# 7_4v_BOOST.net
KiCad netlist of a schematic drawn in Altium Designer
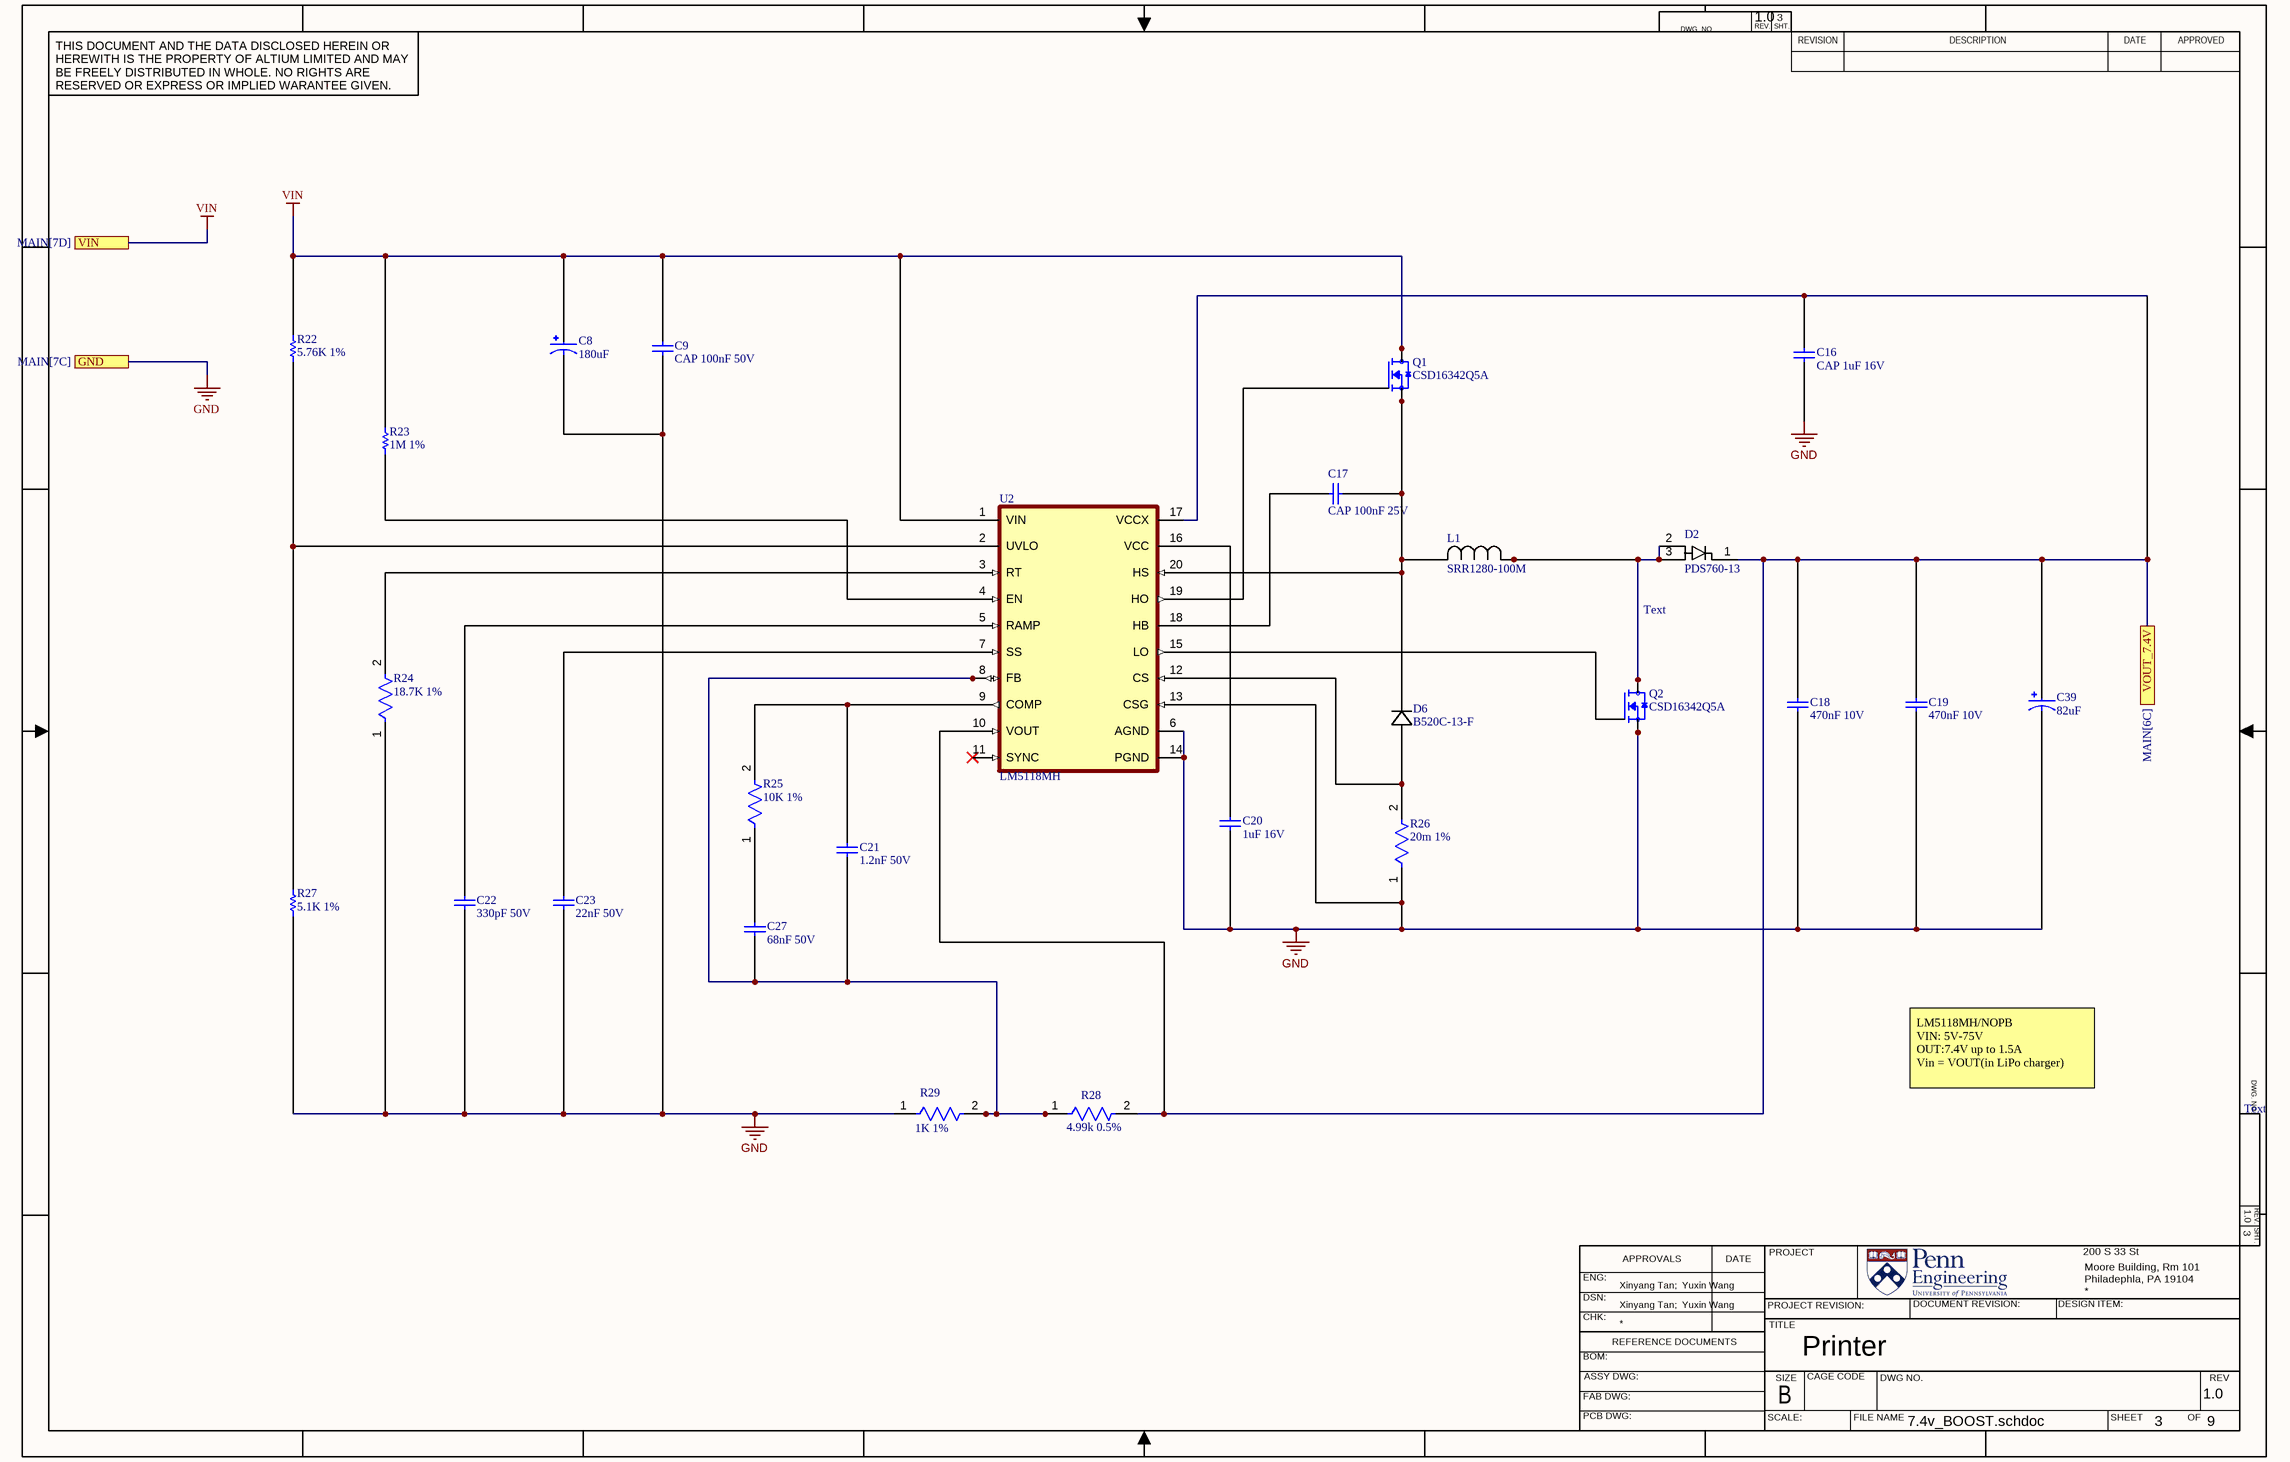
[diagram p0: 7.4v_BOOST.schdoc]

(export (version "E")
  (design (tool "Eeschema 10.0.6"))
  (components
    (comp (ref "C8")
      (value "180uF")
      (footprint "CAP_16SVPF180M")
      (fields (field (name "MP") "16SVPF180M"))
      (libsource (lib "Schematics") (part "16SVPF180M"))
    )
    (comp (ref "C9")
      (value "CAP 100nF 50V")
      (footprint "CAPC0805(2012)100_L")
      (description "CAP 100nF 50V ±5% 0805 (2012 Metric) Thickness 1mm SMD")
      (fields (field (name "TOLERANCE") "Â±5%"))
      (libsource (lib "Altium Content Vault") (part "CAP"))
    )
    (comp (ref "C16")
      (value "CAP 1uF 16V")
      (footprint "CAPC0805(2012)100_N")
      (description "CAP 1uF 16V ±5% 0805 (2012 Metric) Thickness 1mm SMD")
      (fields (field (name "TOLERANCE") "Â±5%"))
      (libsource (lib "Altium Content Vault") (part "CAP"))
    )
    (comp (ref "C17")
      (value "CAP 100nF 25V")
      (footprint "CAPC0805(2012)75_M")
      (description "CAP 100nF 25V ±20% 0805 (2012 Metric) Thickness 0.75mm SMD")
      (fields (field (name "TOLERANCE") "Â±20%"))
      (libsource (lib "Altium Content Vault") (part "CAP"))
    )
    (comp (ref "C18")
      (value "470nF 10V")
      (footprint "CAPC0402(1005)60_M")
      (description "CAP 470nF 10V -20% to +80% 0402 (1005 Metric) Thickness 0.6mm SMD")
      (fields (field (name "TOLERANCE") "-20% to +80%"))
      (libsource (lib "Altium Content Vault") (part "CAP"))
    )
    (comp (ref "C19")
      (value "470nF 10V")
      (footprint "CAPC0402(1005)60_M")
      (description "CAP 470nF 10V -20% to +80% 0402 (1005 Metric) Thickness 0.6mm SMD")
      (fields (field (name "TOLERANCE") "-20% to +80%"))
      (libsource (lib "Altium Content Vault") (part "CAP"))
    )
    (comp (ref "C20")
      (value "1uF 16V")
      (footprint "CAPC0805(2012)100_N")
      (description "CAP 1uF 16V ±5% 0805 (2012 Metric) Thickness 1mm SMD")
      (fields (field (name "TOLERANCE") "Â±5%"))
      (libsource (lib "Altium Content Vault") (part "CAP"))
    )
    (comp (ref "C21")
      (value "1.2nF 50V")
      (footprint "CAPC0805(2012)100_L")
      (description "CAP 1.2nF 50V ±10% 0805 (2012 Metric) Thickness 1mm SMD")
      (fields (field (name "TOLERANCE") "Â±10%"))
      (libsource (lib "Altium Content Vault") (part "CAP"))
    )
    (comp (ref "C22")
      (value "330pF 50V")
      (footprint "CAPC0805(2012)145_L")
      (description "CAP 330pF 50V ±5% 0805 (2012 Metric) Thickness 1.45mm SMD")
      (fields (field (name "TOLERANCE") "Â±5%"))
      (libsource (lib "Altium Content Vault") (part "CAP"))
    )
    (comp (ref "C23")
      (value "22nF 50V")
      (footprint "CAPC0805(2012)75_N")
      (description "CAP 22nF 50V ±20% 0805 (2012 Metric) Thickness 0.75mm SMD")
      (fields (field (name "TOLERANCE") "Â±20%"))
      (libsource (lib "Altium Content Vault") (part "CAP"))
    )
    (comp (ref "C27")
      (value "68nF 50V")
      (footprint "CAPC1206(3216)100_L")
      (description "CAP 68nF 50V -20% to +80% 1206 (3216 Metric) Thickness 1mm SMD")
      (fields (field (name "TOLERANCE") "-20% to +80%"))
      (libsource (lib "Altium Content Vault") (part "CAP"))
    )
    (comp (ref "C39")
      (value "82uF")
      (footprint "CHEMI-F80")
      (description "No Description Available")
      (fields
        (field (name "MANUFACTURER_PART_NUMBER") "APXE160ARA820MF80G")
        (field (name "COPYRIGHT") "Copyright (C) 2022 Ultra Librarian. All rights reserved.")
      )
      (libsource (lib "Schematics") (part "APXE160ARA820MF80G"))
    )
    (comp (ref "D2")
      (value "PDS760-13")
      (footprint "POWERDI5_DIO")
      (description "No Description Available")
      (fields (field (name "COPYRIGHT") "Copyright (C) 2022 Ultra Librarian. All rights reserved."))
      (libsource (lib "Schematics") (part "PDS760-13"))
    )
    (comp (ref "D6")
      (value "B520C-13-F")
      (footprint "SMC_DIO")
      (description "No Description Available")
      (fields (field (name "COPYRIGHT") "Copyright (C) 2022 Ultra Librarian. All rights reserved."))
      (libsource (lib "Schematics") (part "B520C-13-F"))
    )
    (comp (ref "L1")
      (value "SRR1280-100M")
      (footprint "IND_BOURNS_SRR1280")
      (description "No Description Available")
      (fields (field (name "COPYRIGHT") "Copyright (C) 2022 Ultra Librarian. All rights reserved."))
      (libsource (lib "Schematics") (part "SRR1280-100M"))
    )
    (comp (ref "Q1")
      (value "CSD16342Q5A")
      (footprint "DQJ8_TEX")
      (description "No Description Available")
      (fields (field (name "COPYRIGHT") "Copyright (C) 2022 Ultra Librarian. All rights reserved."))
      (libsource (lib "Schematics") (part "CSD16342Q5A"))
    )
    (comp (ref "Q2")
      (value "CSD16342Q5A")
      (footprint "DQJ8_TEX")
      (description "No Description Available")
      (fields (field (name "COPYRIGHT") "Copyright (C) 2022 Ultra Librarian. All rights reserved."))
      (libsource (lib "Schematics") (part "CSD16342Q5A"))
    )
    (comp (ref "R22")
      (value "5.76K 1%")
      (footprint "RESC1608X55X25ML10T15")
      (fields (field (name "PART NUMBER") "RC0603FR-075K76L") (field (name "MANUFACTURER") "Yageo"))
      (libsource (lib "Altium Content Vault") (part "RES"))
    )
    (comp (ref "R23")
      (value "1M 1%")
      (footprint "RESC1608X55X25LL10T15")
      (description "Chip Resistor, 1 MOhm, +/- 1%, 100 mW, -55 to 155 degC, 0603 (1608 Metric), RoHS, Tape and Reel")
      (fields (field (name "TOLERANCE") "20%"))
      (libsource (lib "Altium Content Vault") (part "RES-2"))
    )
    (comp (ref "R24")
      (value "18.7K 1%")
      (footprint "FP-RT0805-MFG")
      (description "RES SMD 18.7K OHM 1% 1/8W 0805")
      (fields
        (field (name "OCTOPART") "https://octopart.com/rt0805fre0718k7l-yageo-1462871")
        (field (name "TOLERANCE") "0.0001")
      )
      (libsource (lib "Altium Content Vault") (part "1029c3af85768c4190bb7ad29bc67b5"))
    )
    (comp (ref "R25")
      (value "10K 1%")
      (footprint "FP-RMCF0402-IPC_C")
      (description "10kΩ ±1% 0.063W 0402 Thick Film Chip Resistor AEC-Q200 compliant")
      (fields (field (name "TOLERANCE") "1%"))
      (libsource (lib "Altium Content Vault") (part "1029c3af85768c4190bb7ad29bc67b5"))
    )
    (comp (ref "R26")
      (value "20m 1%")
      (footprint "FP-PRL1632-IPC_B")
      (description "20 mOhms ±1% 1W Chip Resistor Wide 0612 (1632 Metric), Current Sense Thin Film")
      (fields (field (name "TOLERANCE") "1%"))
      (libsource (lib "Altium Content Vault") (part "1029c3af85768c4190bb7ad29bc67b5"))
    )
    (comp (ref "R27")
      (value "5.1K 1%")
      (footprint "RESC1608X55X25ML10T15")
      (fields (field (name "MANUFACTURER") "Yageo") (field (name "PART NUMBER") "RC0603FR-075K1L"))
      (libsource (lib "Altium Content Vault") (part "RES"))
    )
    (comp (ref "R28")
      (value "4.99k 0.5%")
      (footprint "FP-RG1608-IPC_C")
      (description "Automotive Metal Thin Film Chip Resistor, 0603, 4.99kΩ, 0.5%, 25ppm/°C, 0.1W, 100V")
      (fields (field (name "TOLERANCE") "0.5%"))
      (libsource (lib "Altium Content Vault") (part "1029c3af85768c4190bb7ad29bc67b5"))
    )
    (comp (ref "R29")
      (value "1K 1%")
      (footprint "FP-RC0603-0_55-IPC_C")
      (description "RES 1K OHM 1% 1/10W 0603")
      (fields (field (name "TOLERANCE") "1%"))
      (libsource (lib "Altium Content Vault") (part "1029c3af85768c4190bb7ad29bc67b5"))
    )
    (comp (ref "U2")
      (value "LM5118MH")
      (footprint "MXA20A")
      (fields (field (name "MF") "Texas Instruments"))
      (libsource (lib "Schematics") (part "LM5118MH"))
    )
  )
  (nets
    (net (code "1") (name "/VOUT_7.4V") (class "Default")
      (node (ref "C16") (pin "2") (pinfunction "2_2") (pintype "passive"))
      (node (ref "C18") (pin "2") (pinfunction "2_2") (pintype "passive"))
      (node (ref "C19") (pin "2") (pinfunction "2_2") (pintype "passive"))
      (node (ref "C39") (pin "1") (pinfunction "1_1") (pintype "passive"))
      (node (ref "D2") (pin "1") (pinfunction "1_1") (pintype "passive"))
      (node (ref "R28") (pin "2") (pinfunction "2_2") (pintype "passive"))
      (node (ref "U2") (pin "10") (pinfunction "VOUT_10") (pintype "input"))
      (node (ref "U2") (pin "17") (pinfunction "VCCX_17") (pintype "power_in"))
    )
    (net (code "2") (name "GND") (class "Default")
      (node (ref "C16") (pin "1") (pinfunction "1_1") (pintype "passive"))
      (node (ref "C18") (pin "1") (pinfunction "1_1") (pintype "passive"))
      (node (ref "C19") (pin "1") (pinfunction "1_1") (pintype "passive"))
      (node (ref "C20") (pin "1") (pinfunction "1_1") (pintype "passive"))
      (node (ref "C22") (pin "1") (pinfunction "1_1") (pintype "passive"))
      (node (ref "C23") (pin "1") (pinfunction "1_1") (pintype "passive"))
      (node (ref "C39") (pin "2") (pinfunction "2_2") (pintype "passive"))
      (node (ref "C8") (pin "2") (pinfunction "2_2") (pintype "passive"))
      (node (ref "C9") (pin "1") (pinfunction "1_1") (pintype "passive"))
      (node (ref "Q2") (pin "1") (pinfunction "S_1") (pintype "passive"))
      (node (ref "Q2") (pin "2") (pinfunction "S_2") (pintype "passive"))
      (node (ref "Q2") (pin "3") (pinfunction "S_3") (pintype "passive"))
      (node (ref "R24") (pin "1") (pinfunction "1_1") (pintype "passive"))
      (node (ref "R26") (pin "1") (pinfunction "1_1") (pintype "passive"))
      (node (ref "R27") (pin "1") (pinfunction "1_1") (pintype "passive"))
      (node (ref "R29") (pin "1") (pinfunction "1_1") (pintype "passive"))
      (node (ref "U2") (pin "13") (pinfunction "CSG_13") (pintype "input"))
      (node (ref "U2") (pin "14") (pinfunction "PGND_14") (pintype "passive"))
      (node (ref "U2") (pin "6") (pinfunction "AGND_6") (pintype "passive"))
    )
    (net (code "3") (name "Net-(C27-Pad2)") (class "Default")
      (node (ref "C27") (pin "2") (pinfunction "2_2") (pintype "passive"))
      (node (ref "R25") (pin "1") (pinfunction "1_1") (pintype "passive"))
    )
    (net (code "4") (name "Net-(D2-Pad2)") (class "Default")
      (node (ref "D2") (pin "2") (pinfunction "2_2") (pintype "passive"))
      (node (ref "D2") (pin "3") (pinfunction "3_3") (pintype "passive"))
      (node (ref "L1") (pin "1") (pinfunction "1_1") (pintype "passive"))
      (node (ref "Q2") (pin "5") (pinfunction "D_5") (pintype "passive"))
      (node (ref "Q2") (pin "6") (pinfunction "D_6") (pintype "passive"))
      (node (ref "Q2") (pin "7") (pinfunction "D_7") (pintype "passive"))
      (node (ref "Q2") (pin "8") (pinfunction "D_8") (pintype "passive"))
    )
    (net (code "5") (name "Net-(Q1-G)") (class "Default")
      (node (ref "Q1") (pin "4") (pinfunction "G_4") (pintype "passive"))
      (node (ref "U2") (pin "19") (pinfunction "HO_19") (pintype "output"))
    )
    (net (code "6") (name "Net-(Q2-G)") (class "Default")
      (node (ref "Q2") (pin "4") (pinfunction "G_4") (pintype "passive"))
      (node (ref "U2") (pin "15") (pinfunction "LO_15") (pintype "output"))
    )
    (net (code "7") (name "Net-(U2-COMP)") (class "Default")
      (node (ref "C21") (pin "2") (pinfunction "2_2") (pintype "passive"))
      (node (ref "R25") (pin "2") (pinfunction "2_2") (pintype "passive"))
      (node (ref "U2") (pin "9") (pinfunction "COMP_9") (pintype "output"))
    )
    (net (code "8") (name "Net-(U2-CS)") (class "Default")
      (node (ref "D6") (pin "2") (pinfunction "2_2") (pintype "passive"))
      (node (ref "R26") (pin "2") (pinfunction "2_2") (pintype "passive"))
      (node (ref "U2") (pin "12") (pinfunction "CS_12") (pintype "input"))
    )
    (net (code "9") (name "Net-(U2-EN)") (class "Default")
      (node (ref "R23") (pin "1") (pinfunction "1_1") (pintype "passive"))
      (node (ref "U2") (pin "4") (pinfunction "EN_4") (pintype "input"))
    )
    (net (code "10") (name "Net-(U2-FB)") (class "Default")
      (node (ref "C21") (pin "1") (pinfunction "1_1") (pintype "passive"))
      (node (ref "C27") (pin "1") (pinfunction "1_1") (pintype "passive"))
      (node (ref "R28") (pin "1") (pinfunction "1_1") (pintype "passive"))
      (node (ref "R29") (pin "2") (pinfunction "2_2") (pintype "passive"))
      (node (ref "U2") (pin "8") (pinfunction "FB_8") (pintype "bidirectional"))
    )
    (net (code "11") (name "Net-(U2-HB)") (class "Default")
      (node (ref "C17") (pin "1") (pinfunction "1_1") (pintype "passive"))
      (node (ref "U2") (pin "18") (pinfunction "HB_18") (pintype "power_in"))
    )
    (net (code "12") (name "Net-(U2-HS)") (class "Default")
      (node (ref "C17") (pin "2") (pinfunction "2_2") (pintype "passive"))
      (node (ref "D6") (pin "1") (pinfunction "1_1") (pintype "passive"))
      (node (ref "L1") (pin "2") (pinfunction "2_2") (pintype "passive"))
      (node (ref "Q1") (pin "1") (pinfunction "S_1") (pintype "passive"))
      (node (ref "Q1") (pin "2") (pinfunction "S_2") (pintype "passive"))
      (node (ref "Q1") (pin "3") (pinfunction "S_3") (pintype "passive"))
      (node (ref "U2") (pin "20") (pinfunction "HS_20") (pintype "input"))
    )
    (net (code "13") (name "Net-(U2-RAMP)") (class "Default")
      (node (ref "C22") (pin "2") (pinfunction "2_2") (pintype "passive"))
      (node (ref "U2") (pin "5") (pinfunction "RAMP_5") (pintype "input"))
    )
    (net (code "14") (name "Net-(U2-RT)") (class "Default")
      (node (ref "R24") (pin "2") (pinfunction "2_2") (pintype "passive"))
      (node (ref "U2") (pin "3") (pinfunction "RT_3") (pintype "input"))
    )
    (net (code "15") (name "Net-(U2-SS)") (class "Default")
      (node (ref "C23") (pin "2") (pinfunction "2_2") (pintype "passive"))
      (node (ref "U2") (pin "7") (pinfunction "SS_7") (pintype "input"))
    )
    (net (code "16") (name "Net-(U2-UVLO)") (class "Default")
      (node (ref "R22") (pin "1") (pinfunction "1_1") (pintype "passive"))
      (node (ref "R27") (pin "2") (pinfunction "2_2") (pintype "passive"))
      (node (ref "U2") (pin "2") (pinfunction "UVLO_2") (pintype "passive"))
    )
    (net (code "17") (name "Net-(U2-VCC)") (class "Default")
      (node (ref "C20") (pin "2") (pinfunction "2_2") (pintype "passive"))
      (node (ref "U2") (pin "16") (pinfunction "VCC_16") (pintype "power_in"))
    )
    (net (code "18") (name "VIN") (class "Default")
      (node (ref "C8") (pin "1") (pinfunction "1_1") (pintype "passive"))
      (node (ref "C9") (pin "2") (pinfunction "2_2") (pintype "passive"))
      (node (ref "Q1") (pin "5") (pinfunction "D_5") (pintype "passive"))
      (node (ref "Q1") (pin "6") (pinfunction "D_6") (pintype "passive"))
      (node (ref "Q1") (pin "7") (pinfunction "D_7") (pintype "passive"))
      (node (ref "Q1") (pin "8") (pinfunction "D_8") (pintype "passive"))
      (node (ref "R22") (pin "2") (pinfunction "2_2") (pintype "passive"))
      (node (ref "R23") (pin "2") (pinfunction "2_2") (pintype "passive"))
      (node (ref "U2") (pin "1") (pinfunction "VIN_1") (pintype "power_in"))
    )
    (net (code "19") (name "unconnected-(U2-SYNC-Pad11)") (class "Default")
      (node (ref "U2") (pin "11") (pinfunction "SYNC_11") (pintype "input+no_connect"))
    )
  )
)
